# Power.net
KiCad netlist of a schematic drawn in Altium Designer
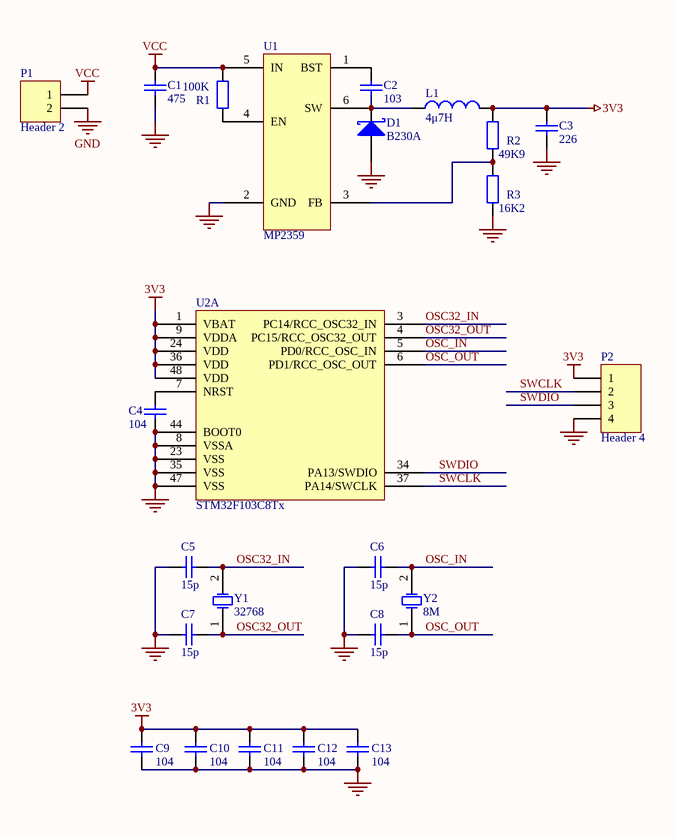
[diagram p0: Power.SchDoc]

(export (version "E")
  (design (tool "Eeschema 10.0.6"))
  (components
    (comp (ref "C1")
      (value "475")
      (footprint "C1206")
      (description "Capacitor")
      (fields (field (name "PUBLISHER") "Altium Limited"))
      (libsource (lib "Miscellaneous Devices") (part "Cap"))
    )
    (comp (ref "C2")
      (value "103")
      (footprint "C0603")
      (description "Capacitor")
      (fields (field (name "PUBLISHER") "Altium Limited"))
      (libsource (lib "Miscellaneous Devices") (part "Cap"))
    )
    (comp (ref "C3")
      (value "226")
      (footprint "C0805")
      (description "Capacitor")
      (fields (field (name "PUBLISHER") "Altium Limited"))
      (libsource (lib "Miscellaneous Devices") (part "Cap"))
    )
    (comp (ref "C4")
      (value "104")
      (footprint "C0603")
      (description "Capacitor")
      (fields (field (name "PUBLISHER") "Altium Limited"))
      (libsource (lib "Miscellaneous Devices") (part "Cap"))
    )
    (comp (ref "C5")
      (value "15p")
      (footprint "C0603")
      (description "Capacitor")
      (fields (field (name "PUBLISHER") "Altium Limited"))
      (libsource (lib "Miscellaneous Devices") (part "Cap"))
    )
    (comp (ref "C6")
      (value "15p")
      (footprint "C0603")
      (description "Capacitor")
      (fields (field (name "PUBLISHER") "Altium Limited"))
      (libsource (lib "Miscellaneous Devices") (part "Cap"))
    )
    (comp (ref "C7")
      (value "15p")
      (footprint "C0603")
      (description "Capacitor")
      (fields (field (name "PUBLISHER") "Altium Limited"))
      (libsource (lib "Miscellaneous Devices") (part "Cap"))
    )
    (comp (ref "C8")
      (value "15p")
      (footprint "C0603")
      (description "Capacitor")
      (fields (field (name "PUBLISHER") "Altium Limited"))
      (libsource (lib "Miscellaneous Devices") (part "Cap"))
    )
    (comp (ref "C9")
      (value "104")
      (footprint "C0603")
      (description "Capacitor")
      (fields (field (name "PUBLISHER") "Altium Limited"))
      (libsource (lib "Miscellaneous Devices") (part "Cap"))
    )
    (comp (ref "C10")
      (value "104")
      (footprint "C0603")
      (description "Capacitor")
      (fields (field (name "PUBLISHER") "Altium Limited"))
      (libsource (lib "Miscellaneous Devices") (part "Cap"))
    )
    (comp (ref "C11")
      (value "104")
      (footprint "C0603")
      (description "Capacitor")
      (fields (field (name "PUBLISHER") "Altium Limited"))
      (libsource (lib "Miscellaneous Devices") (part "Cap"))
    )
    (comp (ref "C12")
      (value "104")
      (footprint "C0603")
      (description "Capacitor")
      (fields (field (name "PUBLISHER") "Altium Limited"))
      (libsource (lib "Miscellaneous Devices") (part "Cap"))
    )
    (comp (ref "C13")
      (value "104")
      (footprint "C0603")
      (description "Capacitor")
      (fields (field (name "PUBLISHER") "Altium Limited"))
      (libsource (lib "Miscellaneous Devices") (part "Cap"))
    )
    (comp (ref "D1")
      (value "B230A")
      (footprint "SMA")
      (description "Silicon AF Schottky Diode for High-Speed Switching")
      (fields (field (name "PUBLISHER") "Altium Limited"))
      (libsource (lib "Miscellaneous Devices") (part "Diode BAS70"))
    )
    (comp (ref "L1")
      (value "4μ7H")
      (footprint "L4X4")
      (fields (field (name "PUBLISHER") "Altium Limited"))
      (libsource (lib "Miscellaneous Devices") (part "Inductor"))
    )
    (comp (ref "P1")
      (value "Header 2")
      (footprint "XH2P54P2")
      (description "Header, 2-Pin, Right Angle")
      (fields (field (name "PUBLISHER") "Altium Limited"))
      (libsource (lib "Miscellaneous Connectors") (part "Header 2H"))
    )
    (comp (ref "P2")
      (value "Header 4")
      (footprint "SIP4")
      (description "Header, 4-Pin")
      (fields (field (name "PUBLISHER") "Altium Limited"))
      (libsource (lib "Miscellaneous Connectors") (part "Header 4"))
    )
    (comp (ref "R1")
      (value "100K")
      (footprint "R0603")
      (description "Resistor")
      (fields (field (name "PUBLISHER") "Altium Limited"))
      (libsource (lib "Miscellaneous Devices") (part "Res2"))
    )
    (comp (ref "R2")
      (value "49K9")
      (footprint "R0603")
      (description "Resistor")
      (fields (field (name "PUBLISHER") "Altium Limited"))
      (libsource (lib "Miscellaneous Devices") (part "Res2"))
    )
    (comp (ref "R3")
      (value "16K2")
      (footprint "R0603")
      (description "Resistor")
      (fields (field (name "PUBLISHER") "Altium Limited"))
      (libsource (lib "Miscellaneous Devices") (part "Res2"))
    )
    (comp (ref "U1") (value "MP2359") (footprint "SOT23-6") (libsource (lib "yinhaonanLib") (part "MP2359")))
    (comp (ref "U2")
      (value "STM32F103C8Tx")
      (footprint "PQFP48")
      (libsource (lib "yinhaonanLib") (part "STM32F103C8Tx"))
    )
    (comp (ref "Y1")
      (value "32768")
      (footprint "FC-135")
      (description "Crystal Oscillator")
      (fields (field (name "PUBLISHER") "Altium Limited"))
      (libsource (lib "Miscellaneous Devices") (part "XTAL"))
    )
    (comp (ref "Y2")
      (value "8M")
      (footprint "CY5032")
      (description "Crystal Oscillator")
      (fields (field (name "PUBLISHER") "Altium Limited"))
      (libsource (lib "Miscellaneous Devices") (part "XTAL"))
    )
  )
  (nets
    (net (code "1") (name "/OSC32_IN") (class "Default")
      (node (ref "C5") (pin "1") (pinfunction "1_1") (pintype "passive"))
      (node (ref "U2") (pin "3") (pinfunction "PC14/RCC_OSC32_IN_3") (pintype "passive"))
      (node (ref "Y1") (pin "2") (pinfunction "OSC2_2") (pintype "passive"))
    )
    (net (code "2") (name "/OSC32_OUT") (class "Default")
      (node (ref "C7") (pin "1") (pinfunction "1_1") (pintype "passive"))
      (node (ref "U2") (pin "4") (pinfunction "PC15/RCC_OSC32_OUT_4") (pintype "passive"))
      (node (ref "Y1") (pin "1") (pinfunction "OSC1_1") (pintype "passive"))
    )
    (net (code "3") (name "/OSC_IN") (class "Default")
      (node (ref "C6") (pin "1") (pinfunction "1_1") (pintype "passive"))
      (node (ref "U2") (pin "5") (pinfunction "PD0/RCC_OSC_IN_5") (pintype "passive"))
      (node (ref "Y2") (pin "2") (pinfunction "OSC2_2") (pintype "passive"))
    )
    (net (code "4") (name "/OSC_OUT") (class "Default")
      (node (ref "C8") (pin "1") (pinfunction "1_1") (pintype "passive"))
      (node (ref "U2") (pin "6") (pinfunction "PD1/RCC_OSC_OUT_6") (pintype "passive"))
      (node (ref "Y2") (pin "1") (pinfunction "OSC1_1") (pintype "passive"))
    )
    (net (code "5") (name "/SWCLK") (class "Default")
      (node (ref "P2") (pin "2") (pinfunction "2_2") (pintype "passive"))
      (node (ref "U2") (pin "37") (pinfunction "PA14/SWCLK_37") (pintype "passive"))
    )
    (net (code "6") (name "/SWDIO") (class "Default")
      (node (ref "P2") (pin "3") (pinfunction "3_3") (pintype "passive"))
      (node (ref "U2") (pin "34") (pinfunction "PA13/SWDIO_34") (pintype "passive"))
    )
    (net (code "7") (name "3V3") (class "Default")
      (node (ref "C10") (pin "2") (pinfunction "2_2") (pintype "passive"))
      (node (ref "C11") (pin "2") (pinfunction "2_2") (pintype "passive"))
      (node (ref "C12") (pin "2") (pinfunction "2_2") (pintype "passive"))
      (node (ref "C13") (pin "2") (pinfunction "2_2") (pintype "passive"))
      (node (ref "C3") (pin "2") (pinfunction "2_2") (pintype "passive"))
      (node (ref "C9") (pin "2") (pinfunction "2_2") (pintype "passive"))
      (node (ref "L1") (pin "2") (pinfunction "2_2") (pintype "passive"))
      (node (ref "P2") (pin "1") (pinfunction "1_1") (pintype "passive"))
      (node (ref "R2") (pin "1") (pinfunction "1_1") (pintype "passive"))
      (node (ref "U2") (pin "1") (pinfunction "VBAT_1") (pintype "passive"))
      (node (ref "U2") (pin "24") (pinfunction "VDD_24") (pintype "passive"))
      (node (ref "U2") (pin "36") (pinfunction "VDD_36") (pintype "passive"))
      (node (ref "U2") (pin "48") (pinfunction "VDD_48") (pintype "passive"))
      (node (ref "U2") (pin "9") (pinfunction "VDDA_9") (pintype "passive"))
    )
    (net (code "8") (name "GND") (class "Default")
      (node (ref "C1") (pin "1") (pinfunction "1_1") (pintype "passive"))
      (node (ref "C10") (pin "1") (pinfunction "1_1") (pintype "passive"))
      (node (ref "C11") (pin "1") (pinfunction "1_1") (pintype "passive"))
      (node (ref "C12") (pin "1") (pinfunction "1_1") (pintype "passive"))
      (node (ref "C13") (pin "1") (pinfunction "1_1") (pintype "passive"))
      (node (ref "C3") (pin "1") (pinfunction "1_1") (pintype "passive"))
      (node (ref "C4") (pin "1") (pinfunction "1_1") (pintype "passive"))
      (node (ref "C5") (pin "2") (pinfunction "2_2") (pintype "passive"))
      (node (ref "C6") (pin "2") (pinfunction "2_2") (pintype "passive"))
      (node (ref "C7") (pin "2") (pinfunction "2_2") (pintype "passive"))
      (node (ref "C8") (pin "2") (pinfunction "2_2") (pintype "passive"))
      (node (ref "C9") (pin "1") (pinfunction "1_1") (pintype "passive"))
      (node (ref "D1") (pin "1") (pinfunction "A_1") (pintype "passive"))
      (node (ref "P1") (pin "2") (pinfunction "2_2") (pintype "passive"))
      (node (ref "P2") (pin "4") (pinfunction "4_4") (pintype "passive"))
      (node (ref "R3") (pin "2") (pinfunction "2_2") (pintype "passive"))
      (node (ref "U1") (pin "2") (pinfunction "GND_2") (pintype "passive"))
      (node (ref "U2") (pin "23") (pinfunction "VSS_23") (pintype "passive"))
      (node (ref "U2") (pin "35") (pinfunction "VSS_35") (pintype "passive"))
      (node (ref "U2") (pin "44") (pinfunction "BOOT0_44") (pintype "passive"))
      (node (ref "U2") (pin "47") (pinfunction "VSS_47") (pintype "passive"))
      (node (ref "U2") (pin "8") (pinfunction "VSSA_8") (pintype "passive"))
    )
    (net (code "9") (name "Net-(D1-K)") (class "Default")
      (node (ref "C2") (pin "1") (pinfunction "1_1") (pintype "passive"))
      (node (ref "D1") (pin "2") (pinfunction "K_2") (pintype "passive"))
      (node (ref "L1") (pin "1") (pinfunction "1_1") (pintype "passive"))
      (node (ref "U1") (pin "6") (pinfunction "SW_6") (pintype "passive"))
    )
    (net (code "10") (name "Net-(U1-BST)") (class "Default")
      (node (ref "C2") (pin "2") (pinfunction "2_2") (pintype "passive"))
      (node (ref "U1") (pin "1") (pinfunction "BST_1") (pintype "passive"))
    )
    (net (code "11") (name "Net-(U1-EN)") (class "Default")
      (node (ref "R1") (pin "2") (pinfunction "2_2") (pintype "passive"))
      (node (ref "U1") (pin "4") (pinfunction "EN_4") (pintype "passive"))
    )
    (net (code "12") (name "Net-(U1-FB)") (class "Default")
      (node (ref "R2") (pin "2") (pinfunction "2_2") (pintype "passive"))
      (node (ref "R3") (pin "1") (pinfunction "1_1") (pintype "passive"))
      (node (ref "U1") (pin "3") (pinfunction "FB_3") (pintype "passive"))
    )
    (net (code "13") (name "Net-(U2A-NRST)") (class "Default")
      (node (ref "C4") (pin "2") (pinfunction "2_2") (pintype "passive"))
      (node (ref "U2") (pin "7") (pinfunction "NRST_7") (pintype "passive"))
    )
    (net (code "14") (name "VCC") (class "Default")
      (node (ref "C1") (pin "2") (pinfunction "2_2") (pintype "passive"))
      (node (ref "P1") (pin "1") (pinfunction "1_1") (pintype "passive"))
      (node (ref "R1") (pin "1") (pinfunction "1_1") (pintype "passive"))
      (node (ref "U1") (pin "5") (pinfunction "IN_5") (pintype "passive"))
    )
  )
)
